# ECGAquisitionBoard.net
KiCad netlist of a schematic drawn in Altium Designer
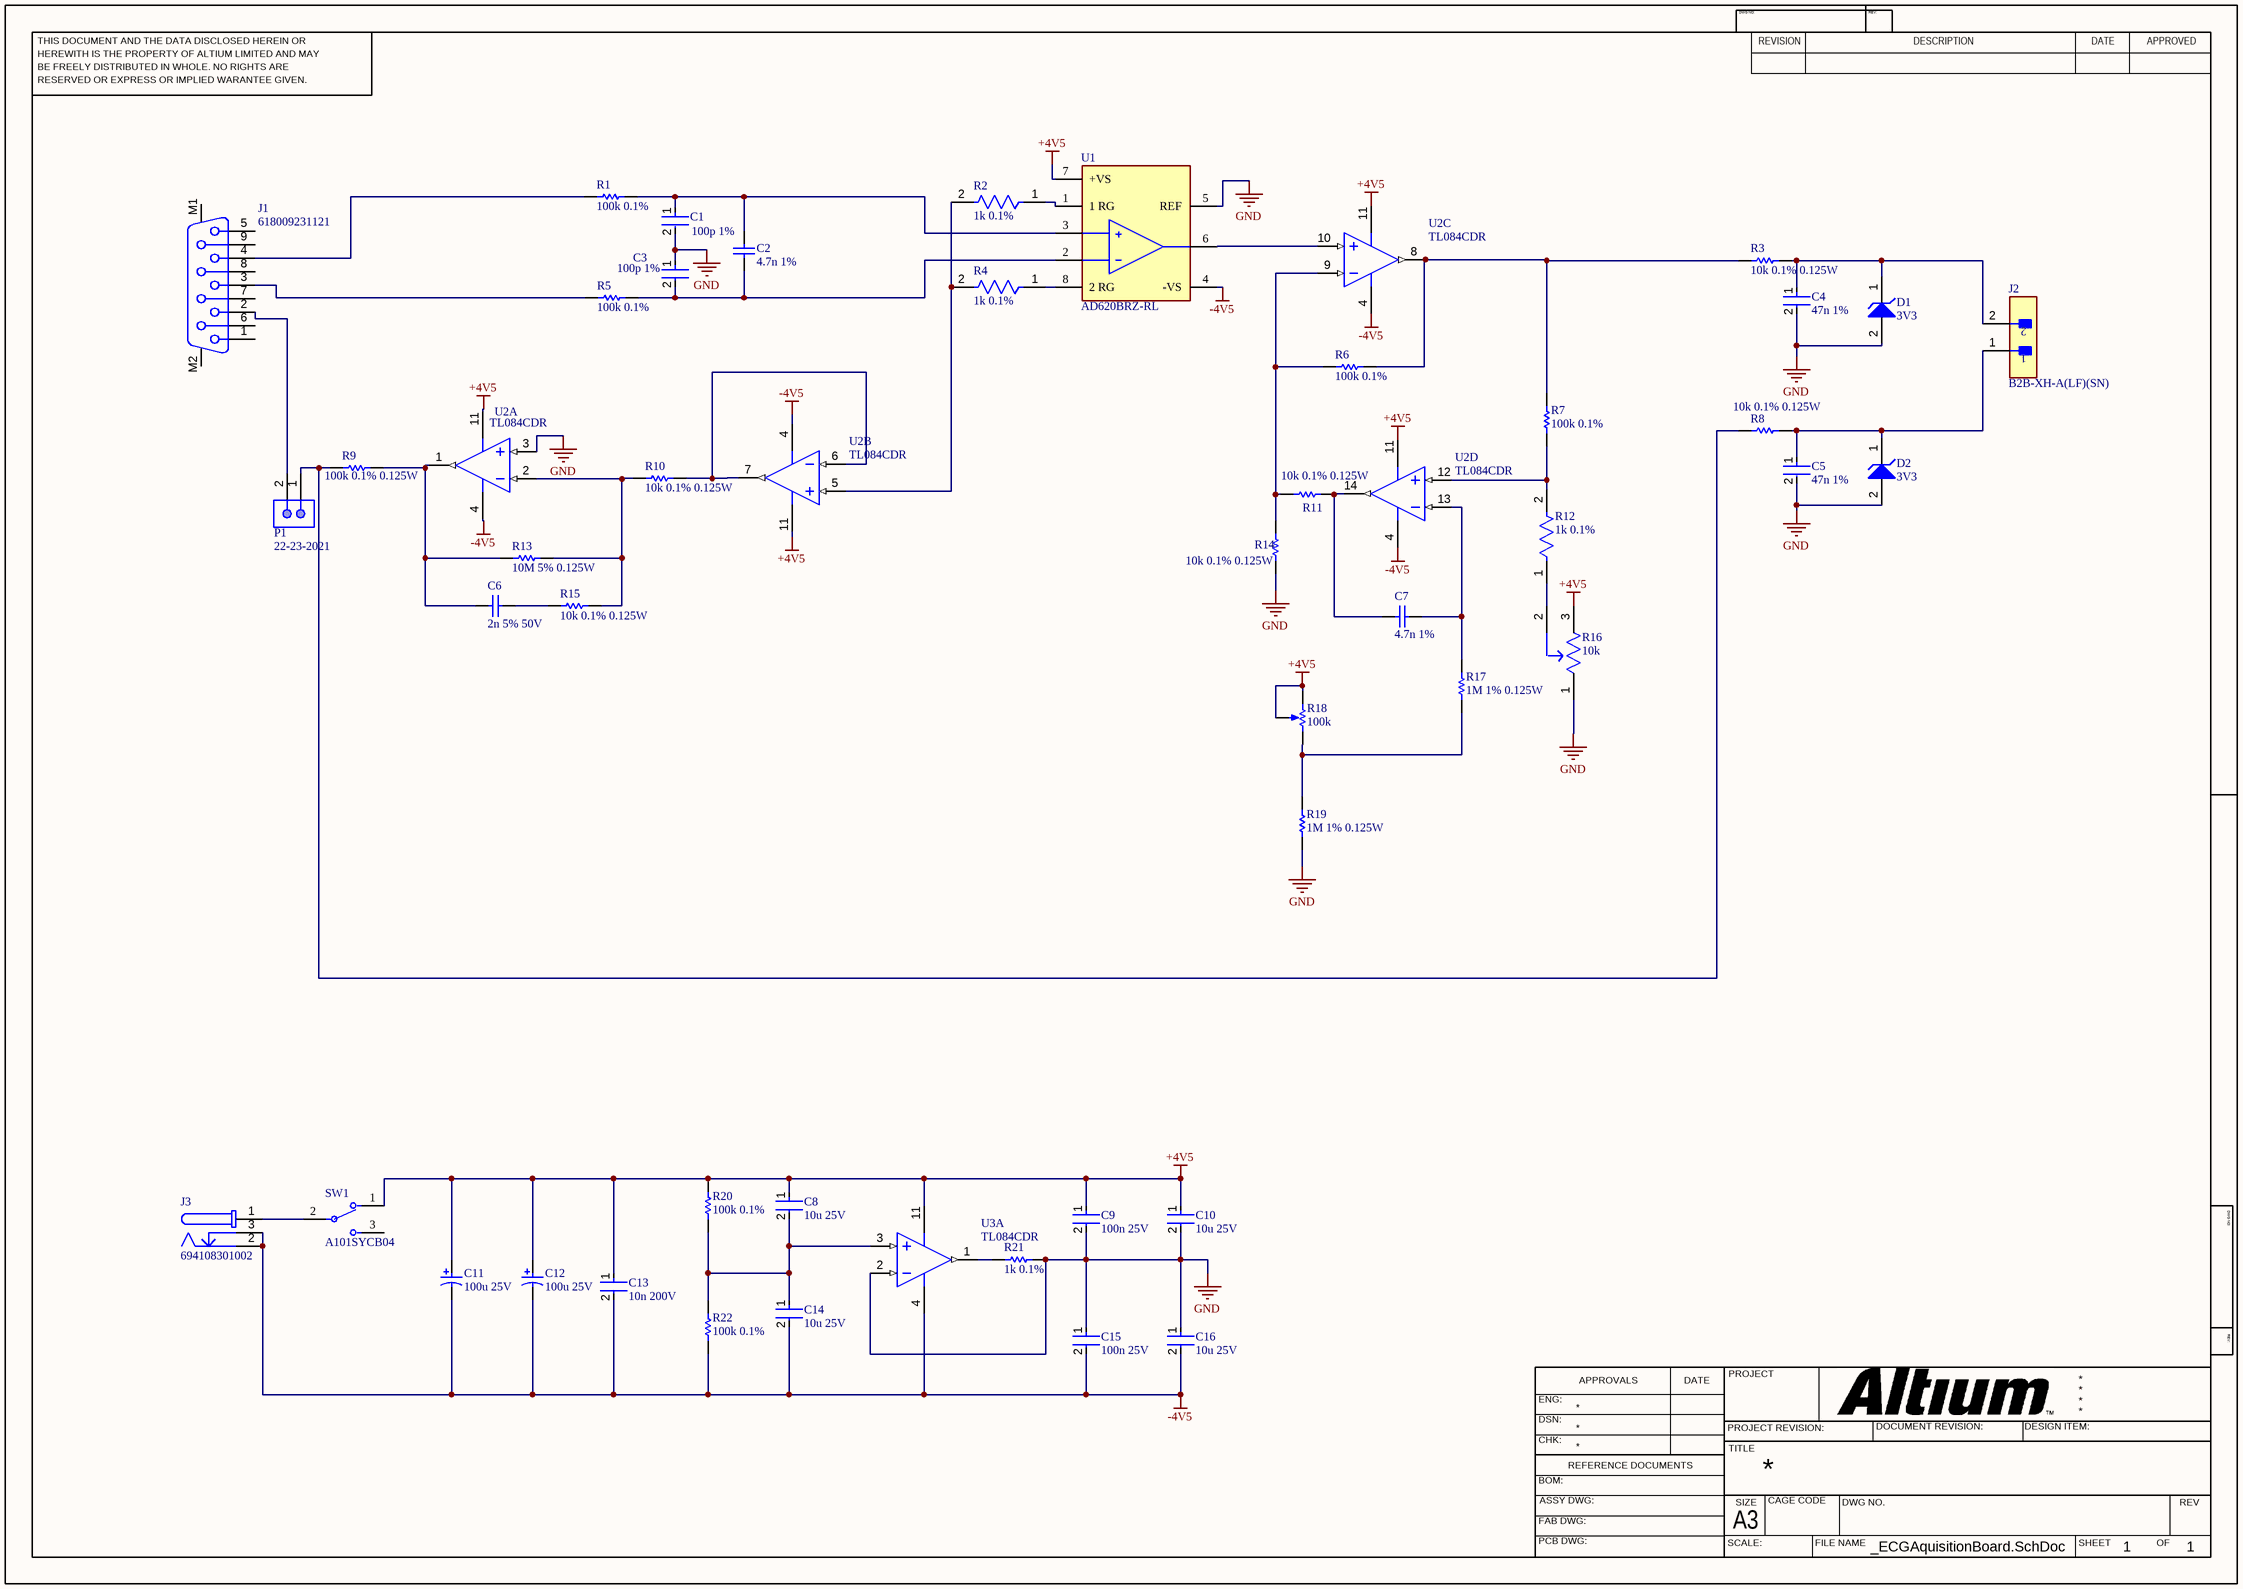
[diagram p0: _ECGAquisitionBoard.SchDoc]

(export (version "E")
  (design (tool "Eeschema 10.0.6"))
  (components
    (comp (ref "C1")
      (value "100p 1%")
      (footprint "FP-0805-L_2_01_0_2-W_1_25-IPC_B")
      (description "General Purpose Ceramic Capacitor, 0805, 100pF, 1%, C0G, 30ppm/°C, 100V")
      (fields (field (name "TOLERANCE") "1%") (field (name "VOLTAGE") "100V"))
      (libsource (lib "Altium Content Vault") (part "02cd4be3c70576c341d710602a673aa"))
    )
    (comp (ref "C2")
      (value "4.7n 1%")
      (footprint "CAPC2013X94X50ML20T25")
      (fields
        (field (name "PART NUMBER") "08053A472FAT2A")
        (field (name "MANUFACTURER") "AVX Interconnect / Elco")
      )
      (libsource (lib "Altium Content Vault") (part "CAP"))
    )
    (comp (ref "C3")
      (value "100p 1%")
      (footprint "FP-0805-L_2_01_0_2-W_1_25-IPC_B")
      (description "General Purpose Ceramic Capacitor, 0805, 100pF, 1%, C0G, 30ppm/°C, 100V")
      (fields (field (name "TOLERANCE") "1%") (field (name "VOLTAGE") "100V"))
      (libsource (lib "Altium Content Vault") (part "02cd4be3c70576c341d710602a673aa"))
    )
    (comp (ref "C4")
      (value "47n 1%")
      (footprint "FP-C1206C-EB-MFG")
      (description "CAP CER 0.047UF 50V NP0 1206")
      (fields (field (name "TOLERANCE") "0.01") (field (name "MANUFACTURER") "KEMET"))
      (libsource (lib "Altium Content Vault") (part "b4654b650e69147ec39a6b967a45e02"))
    )
    (comp (ref "C5")
      (value "47n 1%")
      (footprint "FP-C1206C-EB-MFG")
      (description "CAP CER 0.047UF 50V NP0 1206")
      (fields (field (name "TOLERANCE") "0.01") (field (name "MANUFACTURER") "KEMET"))
      (libsource (lib "Altium Content Vault") (part "b4654b650e69147ec39a6b967a45e02"))
    )
    (comp (ref "C6")
      (value "2n 5% 50V")
      (footprint "CAPC2013X70X45NL10T25")
      (fields (field (name "PART NUMBER") "GRM2165C1H202JA01D") (field (name "MANUFACTURER") "Murata"))
      (libsource (lib "Altium Content Vault") (part "CAP"))
    )
    (comp (ref "C7")
      (value "4.7n 1%")
      (footprint "CAPC2013X94X50ML20T25")
      (fields
        (field (name "PART NUMBER") "08053A472FAT2A")
        (field (name "MANUFACTURER") "AVX Interconnect / Elco")
      )
      (libsource (lib "Altium Content Vault") (part "CAP"))
    )
    (comp (ref "C8")
      (value "10u 25V")
      (footprint "FP-GRM21B-0_15-IPC_C")
      (description "Chip Multilayer Ceramic Capacitors for General Purpose, 0805, 10uF, X5R, 15%, 10%, 25V")
      (fields (field (name "VOLTAGE") "25V") (field (name "TOLERANCE") "10%"))
      (libsource (lib "Altium Content Vault") (part "b4654b650e69147ec39a6b967a45e02"))
    )
    (comp (ref "C9")
      (value "100n 25V")
      (footprint "FP-C0805C-DN-MFG")
      (description "CAP CER 0.1UF 25V 20% X7R 0805")
      (fields (field (name "TOLERANCE") "0.2") (field (name "MANUFACTURER") "KEMET"))
      (libsource (lib "Altium Content Vault") (part "b4654b650e69147ec39a6b967a45e02"))
    )
    (comp (ref "C10")
      (value "10u 25V")
      (footprint "FP-GRM21B-0_15-IPC_C")
      (description "Chip Multilayer Ceramic Capacitors for General Purpose, 0805, 10uF, X5R, 15%, 10%, 25V")
      (fields (field (name "VOLTAGE") "25V") (field (name "TOLERANCE") "10%"))
      (libsource (lib "Altium Content Vault") (part "b4654b650e69147ec39a6b967a45e02"))
    )
    (comp (ref "C11")
      (value "100u 25V")
      (footprint "PNSC-FK-V-D8_V")
      (fields (field (name "MANUFACTURER") "Panasonic"))
      (libsource (lib "Altium Content Vault") (part "CAP-P-2"))
    )
    (comp (ref "C12")
      (value "100u 25V")
      (footprint "PNSC-FK-V-D8_V")
      (fields (field (name "MANUFACTURER") "Panasonic"))
      (libsource (lib "Altium Content Vault") (part "CAP-P-2"))
    )
    (comp (ref "C13")
      (value "10n 200V")
      (footprint "FP-0805-L_2_01_0_2-W_1_25-IPC_A")
      (description "General Purpose Ceramic Capacitor, 0805, 10nF, 10%, X7R, 0.15, 200V")
      (fields (field (name "VOLTAGE") "200V") (field (name "TOLERANCE") "10%"))
      (libsource (lib "Altium Content Vault") (part "02cd4be3c70576c341d710602a673aa"))
    )
    (comp (ref "C14")
      (value "10u 25V")
      (footprint "FP-GRM21B-0_15-IPC_C")
      (description "Chip Multilayer Ceramic Capacitors for General Purpose, 0805, 10uF, X5R, 15%, 10%, 25V")
      (fields (field (name "VOLTAGE") "25V") (field (name "TOLERANCE") "10%"))
      (libsource (lib "Altium Content Vault") (part "b4654b650e69147ec39a6b967a45e02"))
    )
    (comp (ref "C15")
      (value "100n 25V")
      (footprint "FP-C0805C-DN-MFG")
      (description "CAP CER 0.1UF 25V 20% X7R 0805")
      (fields (field (name "TOLERANCE") "0.2") (field (name "MANUFACTURER") "KEMET"))
      (libsource (lib "Altium Content Vault") (part "b4654b650e69147ec39a6b967a45e02"))
    )
    (comp (ref "C16")
      (value "10u 25V")
      (footprint "FP-GRM21B-0_15-IPC_C")
      (description "Chip Multilayer Ceramic Capacitors for General Purpose, 0805, 10uF, X5R, 15%, 10%, 25V")
      (fields (field (name "VOLTAGE") "25V") (field (name "TOLERANCE") "10%"))
      (libsource (lib "Altium Content Vault") (part "b4654b650e69147ec39a6b967a45e02"))
    )
    (comp (ref "D1")
      (value "3V3")
      (footprint "ONSC-SOD-123-2-425-04_V")
      (description "Zener Voltage Regulator, 500 mW, 2-Pin SOD-123, Pb-Free, Tape and Reel")
      (fields (field (name "PARTNUMBER") "MMSZ5226BT1G") (field (name "MANUFACTURER") "On Semiconductor"))
      (libsource (lib "Altium Content Vault") (part "ONSC-K1A2-2"))
    )
    (comp (ref "D2")
      (value "3V3")
      (footprint "ONSC-SOD-123-2-425-04_V")
      (description "Zener Voltage Regulator, 500 mW, 2-Pin SOD-123, Pb-Free, Tape and Reel")
      (fields (field (name "PARTNUMBER") "MMSZ5226BT1G") (field (name "MANUFACTURER") "On Semiconductor"))
      (libsource (lib "Altium Content Vault") (part "ONSC-K1A2-2"))
    )
    (comp (ref "J1")
      (value "618009231121")
      (footprint "618009231121")
      (libsource (lib "Altium Content Vault") (part "D-Sub_Female_09p"))
    )
    (comp (ref "J2")
      (value "B2B-XH-A(LF)(SN)")
      (footprint "FP-B2B-XH-A_LF_SN-MFG")
      (description "CONN HEADER VERT 2POS 2.5MM")
      (libsource (lib "Altium Content Vault") (part "3bc925449376181038e59eaffc5286c"))
    )
    (comp (ref "J3")
      (value "694108301002")
      (footprint "694108301002")
      (libsource (lib "Altium Content Vault") (part "DC Power Jack"))
    )
    (comp (ref "P1")
      (value "22-23-2021")
      (footprint "MOLX-22-23-2021_V")
      (libsource (lib "Altium Content Vault") (part "CN-1P-M-R2"))
    )
    (comp (ref "R1")
      (value "100k 0.1%")
      (footprint "RESC2013X60X40LL20T25_A")
      (fields (field (name "TOLERANCE") "0.1%") (field (name "MANUFACTURER") "Panasonic"))
      (libsource (lib "Altium Content Vault") (part "RES-2"))
    )
    (comp (ref "R2")
      (value "1k 0.1%")
      (footprint "FP-ERA6A-IPC_C")
      (description "RES 1K OHM 0.1% 1/8W 0805")
      (fields (field (name "TOLERANCE") "0.1%"))
      (libsource (lib "Altium Content Vault") (part "1029c3af85768c4190bb7ad29bc67b5"))
    )
    (comp (ref "R3")
      (value "10k 0.1% 0.125W")
      (footprint "RESC2013X60X40LL20T25_A")
      (fields (field (name "TOLERANCE") "0.1%") (field (name "MANUFACTURER") "Panasonic"))
      (libsource (lib "Altium Content Vault") (part "RES-2"))
    )
    (comp (ref "R4")
      (value "1k 0.1%")
      (footprint "FP-ERA6A-IPC_C")
      (description "RES 1K OHM 0.1% 1/8W 0805")
      (fields (field (name "TOLERANCE") "0.1%"))
      (libsource (lib "Altium Content Vault") (part "1029c3af85768c4190bb7ad29bc67b5"))
    )
    (comp (ref "R5")
      (value "100k 0.1%")
      (footprint "RESC2013X60X40LL20T25_A")
      (fields (field (name "TOLERANCE") "0.1%") (field (name "MANUFACTURER") "Panasonic"))
      (libsource (lib "Altium Content Vault") (part "RES-2"))
    )
    (comp (ref "R6")
      (value "100k 0.1%")
      (footprint "RESC2013X60X40LL20T25_A")
      (fields (field (name "TOLERANCE") "0.1%") (field (name "MANUFACTURER") "Panasonic"))
      (libsource (lib "Altium Content Vault") (part "RES-2"))
    )
    (comp (ref "R7")
      (value "100k 0.1%")
      (footprint "RESC2013X60X40LL20T25_A")
      (fields (field (name "TOLERANCE") "0.1%") (field (name "MANUFACTURER") "Panasonic"))
      (libsource (lib "Altium Content Vault") (part "RES-2"))
    )
    (comp (ref "R8")
      (value "10k 0.1% 0.125W")
      (footprint "RESC2013X60X40LL20T25_A")
      (fields (field (name "TOLERANCE") "0.1%") (field (name "MANUFACTURER") "Panasonic"))
      (libsource (lib "Altium Content Vault") (part "RES-2"))
    )
    (comp (ref "R9")
      (value "100k 0.1% 0.125W")
      (footprint "RESC2013X60X40LL20T25_A")
      (fields (field (name "TOLERANCE") "0.1%") (field (name "MANUFACTURER") "Panasonic"))
      (libsource (lib "Altium Content Vault") (part "RES-2"))
    )
    (comp (ref "R10")
      (value "10k 0.1% 0.125W")
      (footprint "RESC2013X60X40LL20T25_A")
      (fields (field (name "TOLERANCE") "0.1%") (field (name "MANUFACTURER") "Panasonic"))
      (libsource (lib "Altium Content Vault") (part "RES-2"))
    )
    (comp (ref "R11")
      (value "10k 0.1% 0.125W")
      (footprint "RESC2013X60X40LL20T25_A")
      (fields (field (name "TOLERANCE") "0.1%") (field (name "MANUFACTURER") "Panasonic"))
      (libsource (lib "Altium Content Vault") (part "RES-2"))
    )
    (comp (ref "R12")
      (value "1k 0.1%")
      (footprint "FP-ERA6A-IPC_C")
      (description "RES 1K OHM 0.1% 1/8W 0805")
      (fields (field (name "TOLERANCE") "0.1%"))
      (libsource (lib "Altium Content Vault") (part "1029c3af85768c4190bb7ad29bc67b5"))
    )
    (comp (ref "R13")
      (value "10M 5% 0.125W")
      (footprint "RESC2013X50X30LL20T20")
      (fields (field (name "PART NUMBER") "CRCW080510M0JNEA") (field (name "MANUFACTURER") "Vishay Dale"))
      (libsource (lib "Altium Content Vault") (part "RES"))
    )
    (comp (ref "R14")
      (value "10k 0.1% 0.125W")
      (footprint "RESC2013X60X40LL20T25_A")
      (fields (field (name "TOLERANCE") "0.1%") (field (name "MANUFACTURER") "Panasonic"))
      (libsource (lib "Altium Content Vault") (part "RES-2"))
    )
    (comp (ref "R15")
      (value "10k 0.1% 0.125W")
      (footprint "RESC2013X60X40LL20T25_A")
      (fields (field (name "TOLERANCE") "0.1%") (field (name "MANUFACTURER") "Panasonic"))
      (libsource (lib "Altium Content Vault") (part "RES-2"))
    )
    (comp (ref "R16")
      (value "10k")
      (footprint "FP-3266W-MFG")
      (description "TRIMMER 10K OHM 0.25W PC PIN TOP")
      (fields
        (field (name "MANUFACTURER") "Bourns")
        (field (name "OCTOPART") "https://octopart.com/3266w-1-103lf-bourns-81445")
      )
      (libsource (lib "Altium Content Vault") (part "5aa38b60e553f01fbee9df648f8b81b"))
    )
    (comp (ref "R17")
      (value "1M 1% 0.125W")
      (footprint "RESC3216X70X50NL05T20")
      (fields (field (name "PART NUMBER") "ERJ-8ENF1004V") (field (name "MANUFACTURER") "Panasonic"))
      (libsource (lib "Altium Content Vault") (part "RES"))
    )
    (comp (ref "R18")
      (value "100k")
      (footprint "BOUR-3266W-3_V")
      (description "Square Trimpot Trimming Potentiometer, 100 KOhm, 0.25 W, -55 to 125 degC, 3-Pin THD, RoHS, Tube")
      (fields (field (name "TOLERANCE") "+/-10%") (field (name "MANUFACTURER") "Bourns"))
      (libsource (lib "Altium Content Vault") (part "BOUR-POT-3"))
    )
    (comp (ref "R19")
      (value "1M 1% 0.125W")
      (footprint "RESC3216X70X50NL05T20")
      (fields (field (name "PART NUMBER") "ERJ-8ENF1004V") (field (name "MANUFACTURER") "Panasonic"))
      (libsource (lib "Altium Content Vault") (part "RES"))
    )
    (comp (ref "R20")
      (value "100k 0.1%")
      (footprint "RESC2013X60X40LL20T25_A")
      (fields (field (name "TOLERANCE") "0.1%") (field (name "MANUFACTURER") "Panasonic"))
      (libsource (lib "Altium Content Vault") (part "RES-2"))
    )
    (comp (ref "R21")
      (value "1k 0.1%")
      (footprint "RESC2013X60X40LL20T25_A")
      (fields (field (name "TOLERANCE") "0.1%") (field (name "MANUFACTURER") "Panasonic"))
      (libsource (lib "Altium Content Vault") (part "RES-2"))
    )
    (comp (ref "R22")
      (value "100k 0.1%")
      (footprint "RESC2013X60X40LL20T25_A")
      (fields (field (name "TOLERANCE") "0.1%") (field (name "MANUFACTURER") "Panasonic"))
      (libsource (lib "Altium Content Vault") (part "RES-2"))
    )
    (comp (ref "SW1")
      (value "A101SYCB04")
      (footprint "FP-A101SYCB04-MFG")
      (description "SWITCH TOGGLE SPDT 0.4VA 20V")
      (libsource (lib "Altium Content Vault") (part "52c419afdc2a387c7d548259a9aeefb"))
    )
    (comp (ref "U1")
      (value "AD620BRZ-RL")
      (footprint "FP-R-8-IPC_A")
      (description "IC INST AMP 1 CIRCUIT 8SOIC")
      (libsource (lib "Altium Content Vault") (part "b1ca39593d8cc57aa2599e6d86efae1"))
    )
    (comp (ref "U2")
      (value "TL084CDR")
      (footprint "D0014A_N")
      (fields (field (name "MANUFACTURER") "Texas Instruments"))
      (libsource (lib "Altium Content Vault") (part "TI-TLXX4X_MC3403-X14"))
    )
    (comp (ref "U3")
      (value "TL084CDR")
      (footprint "D0014A_N")
      (fields (field (name "MANUFACTURER") "Texas Instruments"))
      (libsource (lib "Altium Content Vault") (part "TI-TLXX4X_MC3403-X14"))
    )
  )
  (nets
    (net (code "1") (name "+4V5") (class "Default")
      (node (ref "C10") (pin "1") (pinfunction "1_1") (pintype "passive"))
      (node (ref "C11") (pin "1") (pinfunction "1_1") (pintype "passive"))
      (node (ref "C12") (pin "1") (pinfunction "1_1") (pintype "passive"))
      (node (ref "C13") (pin "1") (pinfunction "1_1") (pintype "passive"))
      (node (ref "C8") (pin "1") (pinfunction "1_1") (pintype "passive"))
      (node (ref "C9") (pin "1") (pinfunction "1_1") (pintype "passive"))
      (node (ref "R16") (pin "3") (pinfunction "CW_3") (pintype "passive"))
      (node (ref "R18") (pin "1") (pinfunction "CCW_1") (pintype "passive"))
      (node (ref "R18") (pin "2") (pinfunction "WIPER_2") (pintype "passive"))
      (node (ref "R20") (pin "2") (pinfunction "2_2") (pintype "passive"))
      (node (ref "SW1") (pin "1") (pinfunction "1_1") (pintype "passive"))
      (node (ref "U1") (pin "7") (pinfunction "+VS_7") (pintype "power_in"))
      (node (ref "U2") (pin "11") (pinfunction "VCC-_11") (pintype "power_in"))
      (node (ref "U3") (pin "11") (pinfunction "VCC-_11") (pintype "power_in"))
    )
    (net (code "2") (name "-4V5") (class "Default")
      (node (ref "C11") (pin "2") (pinfunction "2_2") (pintype "passive"))
      (node (ref "C12") (pin "2") (pinfunction "2_2") (pintype "passive"))
      (node (ref "C13") (pin "2") (pinfunction "2_2") (pintype "passive"))
      (node (ref "C14") (pin "2") (pinfunction "2_2") (pintype "passive"))
      (node (ref "C15") (pin "2") (pinfunction "2_2") (pintype "passive"))
      (node (ref "C16") (pin "2") (pinfunction "2_2") (pintype "passive"))
      (node (ref "J3") (pin "2") (pinfunction "2_2") (pintype "passive"))
      (node (ref "J3") (pin "3") (pinfunction "3_3") (pintype "passive"))
      (node (ref "R22") (pin "1") (pinfunction "1_1") (pintype "passive"))
      (node (ref "U1") (pin "4") (pinfunction "-VS_4") (pintype "power_in"))
      (node (ref "U2") (pin "4") (pinfunction "VCC+_4") (pintype "power_in"))
      (node (ref "U3") (pin "4") (pinfunction "VCC+_4") (pintype "power_in"))
    )
    (net (code "3") (name "GND") (class "Default")
      (node (ref "C1") (pin "2") (pinfunction "2_2") (pintype "passive"))
      (node (ref "C10") (pin "2") (pinfunction "2_2") (pintype "passive"))
      (node (ref "C15") (pin "1") (pinfunction "1_1") (pintype "passive"))
      (node (ref "C16") (pin "1") (pinfunction "1_1") (pintype "passive"))
      (node (ref "C3") (pin "1") (pinfunction "1_1") (pintype "passive"))
      (node (ref "C4") (pin "2") (pinfunction "2_2") (pintype "passive"))
      (node (ref "C5") (pin "2") (pinfunction "2_2") (pintype "passive"))
      (node (ref "C9") (pin "2") (pinfunction "2_2") (pintype "passive"))
      (node (ref "D1") (pin "2") (pinfunction "A_2") (pintype "passive"))
      (node (ref "D2") (pin "2") (pinfunction "A_2") (pintype "passive"))
      (node (ref "R14") (pin "1") (pinfunction "1_1") (pintype "passive"))
      (node (ref "R16") (pin "1") (pinfunction "CCW_1") (pintype "passive"))
      (node (ref "R19") (pin "1") (pinfunction "1_1") (pintype "passive"))
      (node (ref "R21") (pin "1") (pinfunction "1_1") (pintype "passive"))
      (node (ref "U1") (pin "5") (pinfunction "REF_5") (pintype "passive"))
      (node (ref "U2") (pin "3") (pinfunction "IN1+_3") (pintype "input"))
      (node (ref "U3") (pin "2") (pinfunction "IN1-_2") (pintype "input"))
    )
    (net (code "4") (name "Net-(C6-Pad2)") (class "Default")
      (node (ref "C6") (pin "2") (pinfunction "2_2") (pintype "passive"))
      (node (ref "R15") (pin "2") (pinfunction "2_2") (pintype "passive"))
    )
    (net (code "5") (name "Net-(D1-K)") (class "Default")
      (node (ref "C4") (pin "1") (pinfunction "1_1") (pintype "passive"))
      (node (ref "D1") (pin "1") (pinfunction "K_1") (pintype "passive"))
      (node (ref "J2") (pin "2") (pinfunction "2_2") (pintype "passive"))
      (node (ref "R3") (pin "1") (pinfunction "1_1") (pintype "passive"))
    )
    (net (code "6") (name "Net-(D2-K)") (class "Default")
      (node (ref "C5") (pin "1") (pinfunction "1_1") (pintype "passive"))
      (node (ref "D2") (pin "1") (pinfunction "K_1") (pintype "passive"))
      (node (ref "J2") (pin "1") (pinfunction "1_1") (pintype "passive"))
      (node (ref "R8") (pin "1") (pinfunction "1_1") (pintype "passive"))
    )
    (net (code "7") (name "Net-(J1-Pad2)") (class "Default")
      (node (ref "J1") (pin "2") (pinfunction "2_2") (pintype "passive"))
      (node (ref "P1") (pin "2") (pinfunction "2_2") (pintype "passive"))
    )
    (net (code "8") (name "Net-(J1-Pad3)") (class "Default")
      (node (ref "J1") (pin "3") (pinfunction "3_3") (pintype "passive"))
      (node (ref "R5") (pin "2") (pinfunction "2_2") (pintype "passive"))
    )
    (net (code "9") (name "Net-(J1-Pad4)") (class "Default")
      (node (ref "J1") (pin "4") (pinfunction "4_4") (pintype "passive"))
      (node (ref "R1") (pin "2") (pinfunction "2_2") (pintype "passive"))
    )
    (net (code "10") (name "Net-(J3-Pad1)") (class "Default")
      (node (ref "J3") (pin "1") (pinfunction "1_1") (pintype "passive"))
      (node (ref "SW1") (pin "2") (pinfunction "2_2") (pintype "passive"))
    )
    (net (code "11") (name "Net-(P1-Pad1)") (class "Default")
      (node (ref "P1") (pin "1") (pinfunction "1_1") (pintype "passive"))
      (node (ref "R8") (pin "2") (pinfunction "2_2") (pintype "passive"))
      (node (ref "R9") (pin "2") (pinfunction "2_2") (pintype "passive"))
    )
    (net (code "12") (name "Net-(R16-WIPER)") (class "Default")
      (node (ref "R12") (pin "1") (pinfunction "1_1") (pintype "passive"))
      (node (ref "R16") (pin "2") (pinfunction "WIPER_2") (pintype "passive"))
    )
    (net (code "13") (name "Net-(R18-CW)") (class "Default")
      (node (ref "R17") (pin "1") (pinfunction "1_1") (pintype "passive"))
      (node (ref "R18") (pin "3") (pinfunction "CW_3") (pintype "passive"))
      (node (ref "R19") (pin "2") (pinfunction "2_2") (pintype "passive"))
    )
    (net (code "14") (name "Net-(U1-+IN)") (class "Default")
      (node (ref "C1") (pin "1") (pinfunction "1_1") (pintype "passive"))
      (node (ref "C2") (pin "2") (pinfunction "2_2") (pintype "passive"))
      (node (ref "R1") (pin "1") (pinfunction "1_1") (pintype "passive"))
      (node (ref "U1") (pin "3") (pinfunction "+IN_3") (pintype "tri_state"))
    )
    (net (code "15") (name "Net-(U1--IN)") (class "Default")
      (node (ref "C2") (pin "1") (pinfunction "1_1") (pintype "passive"))
      (node (ref "C3") (pin "2") (pinfunction "2_2") (pintype "passive"))
      (node (ref "R5") (pin "1") (pinfunction "1_1") (pintype "passive"))
      (node (ref "U1") (pin "2") (pinfunction "-IN_2") (pintype "tri_state"))
    )
    (net (code "16") (name "Net-(U1-1_RG)") (class "Default")
      (node (ref "R2") (pin "1") (pinfunction "1_1") (pintype "passive"))
      (node (ref "U1") (pin "1") (pinfunction "1_RG_1") (pintype "passive"))
    )
    (net (code "17") (name "Net-(U1-2_RG)") (class "Default")
      (node (ref "R4") (pin "1") (pinfunction "1_1") (pintype "passive"))
      (node (ref "U1") (pin "8") (pinfunction "2_RG_8") (pintype "passive"))
    )
    (net (code "18") (name "Net-(U1-OUTPUT)") (class "Default")
      (node (ref "U1") (pin "6") (pinfunction "OUTPUT_6") (pintype "passive"))
      (node (ref "U2") (pin "10") (pinfunction "IN3+_10") (pintype "input"))
    )
    (net (code "19") (name "Net-(U2A-IN1-)") (class "Default")
      (node (ref "R10") (pin "2") (pinfunction "2_2") (pintype "passive"))
      (node (ref "R13") (pin "2") (pinfunction "2_2") (pintype "passive"))
      (node (ref "R15") (pin "1") (pinfunction "1_1") (pintype "passive"))
      (node (ref "U2") (pin "2") (pinfunction "IN1-_2") (pintype "input"))
    )
    (net (code "20") (name "Net-(U2A-OUT1)") (class "Default")
      (node (ref "C6") (pin "1") (pinfunction "1_1") (pintype "passive"))
      (node (ref "R13") (pin "1") (pinfunction "1_1") (pintype "passive"))
      (node (ref "R9") (pin "1") (pinfunction "1_1") (pintype "passive"))
      (node (ref "U2") (pin "1") (pinfunction "OUT1_1") (pintype "output"))
    )
    (net (code "21") (name "Net-(U2B-IN2+)") (class "Default")
      (node (ref "R2") (pin "2") (pinfunction "2_2") (pintype "passive"))
      (node (ref "R4") (pin "2") (pinfunction "2_2") (pintype "passive"))
      (node (ref "U2") (pin "5") (pinfunction "IN2+_5") (pintype "input"))
    )
    (net (code "22") (name "Net-(U2B-IN2-)") (class "Default")
      (node (ref "R10") (pin "1") (pinfunction "1_1") (pintype "passive"))
      (node (ref "U2") (pin "6") (pinfunction "IN2-_6") (pintype "input"))
      (node (ref "U2") (pin "7") (pinfunction "OUT2_7") (pintype "output"))
    )
    (net (code "23") (name "Net-(U2C-IN3-)") (class "Default")
      (node (ref "R11") (pin "2") (pinfunction "2_2") (pintype "passive"))
      (node (ref "R14") (pin "2") (pinfunction "2_2") (pintype "passive"))
      (node (ref "R6") (pin "2") (pinfunction "2_2") (pintype "passive"))
      (node (ref "U2") (pin "9") (pinfunction "IN3-_9") (pintype "input"))
    )
    (net (code "24") (name "Net-(U2C-OUT3)") (class "Default")
      (node (ref "R3") (pin "2") (pinfunction "2_2") (pintype "passive"))
      (node (ref "R6") (pin "1") (pinfunction "1_1") (pintype "passive"))
      (node (ref "R7") (pin "1") (pinfunction "1_1") (pintype "passive"))
      (node (ref "U2") (pin "8") (pinfunction "OUT3_8") (pintype "output"))
    )
    (net (code "25") (name "Net-(U2D-IN4+)") (class "Default")
      (node (ref "R12") (pin "2") (pinfunction "2_2") (pintype "passive"))
      (node (ref "R7") (pin "2") (pinfunction "2_2") (pintype "passive"))
      (node (ref "U2") (pin "12") (pinfunction "IN4+_12") (pintype "input"))
    )
    (net (code "26") (name "Net-(U2D-IN4-)") (class "Default")
      (node (ref "C7") (pin "1") (pinfunction "1_1") (pintype "passive"))
      (node (ref "R17") (pin "2") (pinfunction "2_2") (pintype "passive"))
      (node (ref "U2") (pin "13") (pinfunction "IN4-_13") (pintype "input"))
    )
    (net (code "27") (name "Net-(U2D-OUT4)") (class "Default")
      (node (ref "C7") (pin "2") (pinfunction "2_2") (pintype "passive"))
      (node (ref "R11") (pin "1") (pinfunction "1_1") (pintype "passive"))
      (node (ref "U2") (pin "14") (pinfunction "OUT4_14") (pintype "output"))
    )
    (net (code "28") (name "Net-(U3A-IN1+)") (class "Default")
      (node (ref "C14") (pin "1") (pinfunction "1_1") (pintype "passive"))
      (node (ref "C8") (pin "2") (pinfunction "2_2") (pintype "passive"))
      (node (ref "R20") (pin "1") (pinfunction "1_1") (pintype "passive"))
      (node (ref "R22") (pin "2") (pinfunction "2_2") (pintype "passive"))
      (node (ref "U3") (pin "3") (pinfunction "IN1+_3") (pintype "input"))
    )
    (net (code "29") (name "Net-(U3A-OUT1)") (class "Default")
      (node (ref "R21") (pin "2") (pinfunction "2_2") (pintype "passive"))
      (node (ref "U3") (pin "1") (pinfunction "OUT1_1") (pintype "output"))
    )
    (net (code "30") (name "unconnected-(J1-Pad1)") (class "Default")
      (node (ref "J1") (pin "1") (pinfunction "1_1") (pintype "passive"))
    )
    (net (code "31") (name "unconnected-(J1-Pad5)") (class "Default")
      (node (ref "J1") (pin "5") (pinfunction "5_5") (pintype "passive"))
    )
    (net (code "32") (name "unconnected-(J1-Pad6)") (class "Default")
      (node (ref "J1") (pin "6") (pinfunction "6_6") (pintype "passive"))
    )
    (net (code "33") (name "unconnected-(J1-Pad7)") (class "Default")
      (node (ref "J1") (pin "7") (pinfunction "7_7") (pintype "passive"))
    )
    (net (code "34") (name "unconnected-(J1-Pad8)") (class "Default")
      (node (ref "J1") (pin "8") (pinfunction "8_8") (pintype "passive"))
    )
    (net (code "35") (name "unconnected-(J1-Pad9)") (class "Default")
      (node (ref "J1") (pin "9") (pinfunction "9_9") (pintype "passive"))
    )
    (net (code "36") (name "unconnected-(J1-PadM1)") (class "Default")
      (node (ref "J1") (pin "M1") (pinfunction "M1_M1") (pintype "passive"))
    )
    (net (code "37") (name "unconnected-(J1-PadM2)") (class "Default")
      (node (ref "J1") (pin "M2") (pinfunction "M2_M2") (pintype "passive"))
    )
    (net (code "38") (name "unconnected-(SW1-Pad3)") (class "Default")
      (node (ref "SW1") (pin "3") (pinfunction "3_3") (pintype "passive"))
    )
  )
)
